# usbswitch.net
KiCad netlist of a schematic drawn in EAGLE
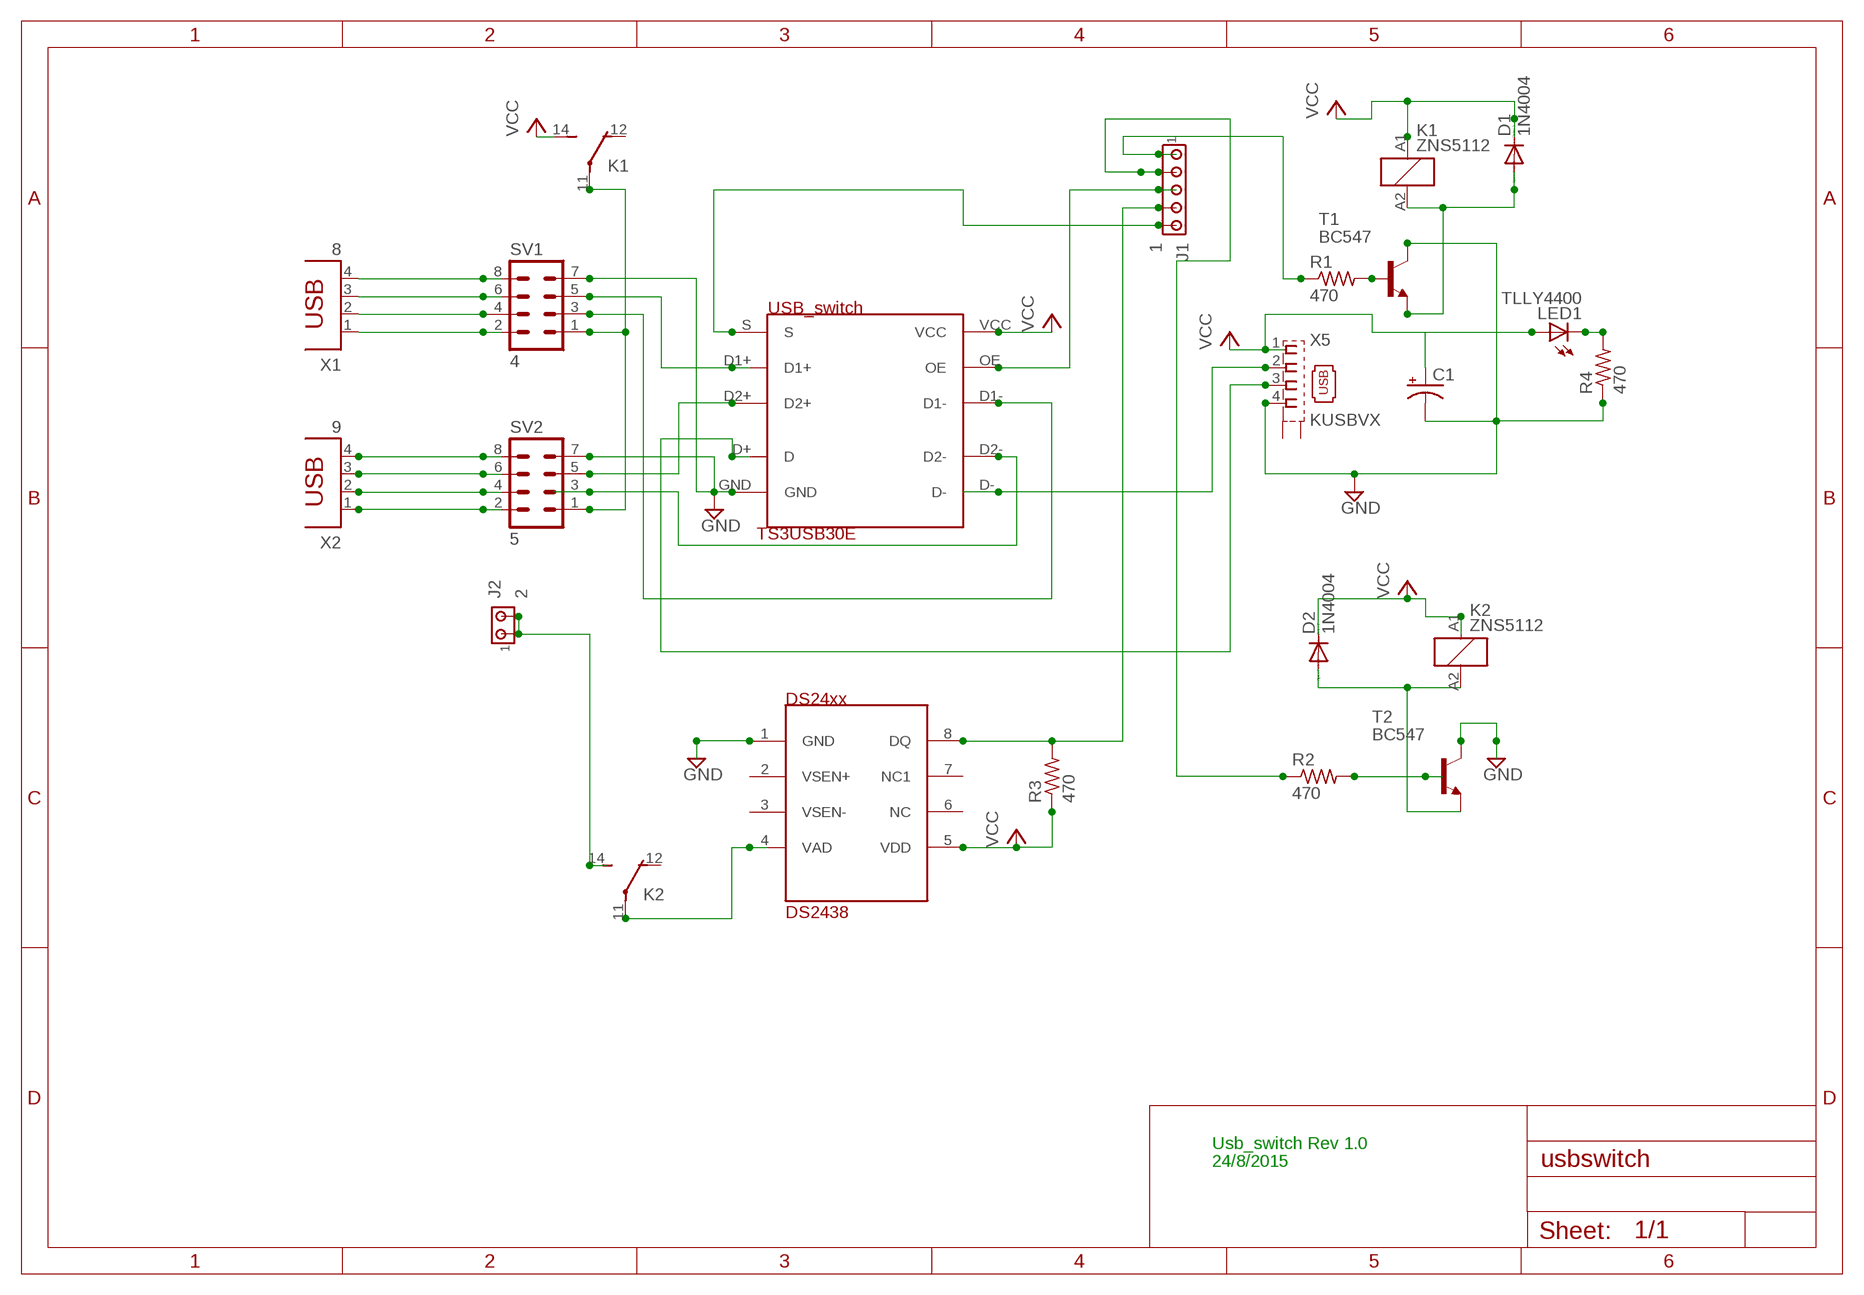
[diagram p0: schematic, sheet 1]

(export (version "E")
  (design (tool "Eeschema 10.0.6"))
  (components
    (comp (ref "C1")
      (value "CPOL-USB45181A")
      (footprint "eagle-import:B45181A")
      (libsource (lib "eagle-import") (part "CPOL-USB45181A"))
    )
    (comp (ref "D1")
      (value "1N4004")
      (footprint "eagle-import:DO41-10")
      (libsource (lib "eagle-import") (part "1N4004"))
    )
    (comp (ref "D2")
      (value "1N4004")
      (footprint "eagle-import:DO41-10")
      (libsource (lib "eagle-import") (part "1N4004"))
    )
    (comp (ref "J1")
      (value "1")
      (footprint "eagle-import:10X05MTA")
      (libsource (lib "eagle-import") (part "MTA05-100"))
    )
    (comp (ref "J2")
      (value "2")
      (footprint "eagle-import:1X2MTA")
      (libsource (lib "eagle-import") (part "MTA02-156"))
    )
    (comp (ref "K1")
      (value "ZNS5112")
      (footprint "eagle-import:ZN5")
      (libsource (lib "eagle-import") (part "ZNS5112"))
    )
    (comp (ref "K2")
      (value "ZNS5112")
      (footprint "eagle-import:ZN5")
      (libsource (lib "eagle-import") (part "ZNS5112"))
    )
    (comp (ref "LED1")
      (value "TLLY4400")
      (footprint "eagle-import:LED3MM")
      (fields (field (name "MF") "VISHAY SEMICONDUCTOR"))
      (libsource (lib "eagle-import") (part "TLLY4400"))
    )
    (comp (ref "R1")
      (value "470")
      (footprint "eagle-import:0204_5")
      (libsource (lib "eagle-import") (part "R-US_0204/5"))
    )
    (comp (ref "R2")
      (value "470")
      (footprint "eagle-import:0204_5")
      (libsource (lib "eagle-import") (part "R-US_0204/5"))
    )
    (comp (ref "R3")
      (value "470")
      (footprint "eagle-import:0204_5")
      (libsource (lib "eagle-import") (part "R-US_0204/5"))
    )
    (comp (ref "R4")
      (value "470")
      (footprint "eagle-import:0204_5")
      (libsource (lib "eagle-import") (part "R-US_0204/5"))
    )
    (comp (ref "SV1")
      (value "4")
      (footprint "eagle-import:MA04-2")
      (libsource (lib "eagle-import") (part "MA04-2"))
    )
    (comp (ref "SV2")
      (value "5")
      (footprint "eagle-import:MA04-2")
      (libsource (lib "eagle-import") (part "MA04-2"))
    )
    (comp (ref "T1")
      (value "BC547")
      (footprint "eagle-import:TO92")
      (libsource (lib "eagle-import") (part "BC547"))
    )
    (comp (ref "T2")
      (value "BC547")
      (footprint "eagle-import:TO92")
      (libsource (lib "eagle-import") (part "BC547"))
    )
    (comp (ref "U$1")
      (value "USB_SWITCH")
      (footprint "eagle-import:PDSO-G10")
      (libsource (lib "eagle-import") (part "myusbswitch_USB_SWITCH"))
    )
    (comp (ref "U$2")
      (value "DS2438")
      (footprint "eagle-import:DS243PKG")
      (libsource (lib "eagle-import") (part "DS2438"))
    )
    (comp (ref "X1")
      (value "8")
      (footprint "eagle-import:PN87520")
      (libsource (lib "eagle-import") (part "PN87520"))
    )
    (comp (ref "X2")
      (value "9")
      (footprint "eagle-import:PN87520")
      (libsource (lib "eagle-import") (part "PN87520"))
    )
    (comp (ref "X5")
      (value "KUSBVX")
      (footprint "eagle-import:KUSBVX")
      (libsource (lib "eagle-import") (part "KUSBVX"))
    )
  )
  (nets
    (net (code "1") (name "GND") (class "Default")
      (node (ref "C1") (pin "-") (pinfunction "-_-") (pintype "passive"))
      (node (ref "R4") (pin "1") (pinfunction "1_1") (pintype "passive"))
      (node (ref "SV1") (pin "7") (pinfunction "7_7") (pintype "passive"))
      (node (ref "SV2") (pin "7") (pinfunction "7_7") (pintype "passive"))
      (node (ref "T1") (pin "3") (pinfunction "C_3") (pintype "passive"))
      (node (ref "T2") (pin "3") (pinfunction "C_3") (pintype "passive"))
      (node (ref "U$1") (pin "GND") (pinfunction "GND_GND") (pintype "bidirectional"))
      (node (ref "U$2") (pin "1") (pinfunction "GND_1") (pintype "bidirectional"))
      (node (ref "X5") (pin "4") (pinfunction "4_4") (pintype "passive"))
    )
    (net (code "2") (name "Net-(J1-Pad1)") (class "Default")
      (node (ref "J1") (pin "1") (pinfunction "1_1") (pintype "passive"))
      (node (ref "R1") (pin "1") (pinfunction "1_1") (pintype "passive"))
    )
    (net (code "3") (name "Net-(J1-Pad2)") (class "Default")
      (node (ref "J1") (pin "2") (pinfunction "2_2") (pintype "passive"))
      (node (ref "R2") (pin "1") (pinfunction "1_1") (pintype "passive"))
    )
    (net (code "4") (name "Net-(J1-Pad3)") (class "Default")
      (node (ref "J1") (pin "3") (pinfunction "3_3") (pintype "passive"))
      (node (ref "U$1") (pin "OE") (pinfunction "OE_OE") (pintype "bidirectional"))
    )
    (net (code "5") (name "Net-(J1-Pad5)") (class "Default")
      (node (ref "J1") (pin "5") (pinfunction "5_5") (pintype "passive"))
      (node (ref "U$1") (pin "S") (pinfunction "S_S") (pintype "bidirectional"))
    )
    (net (code "6") (name "Net-(K1A-2)") (class "Default")
      (node (ref "D1") (pin "A") (pinfunction "A_A") (pintype "passive"))
      (node (ref "K1") (pin "A2") (pinfunction "2_A2") (pintype "passive"))
      (node (ref "T1") (pin "1") (pinfunction "E_1") (pintype "passive"))
    )
    (net (code "7") (name "Net-(K1B-P)") (class "Default")
      (node (ref "K1") (pin "11") (pinfunction "P_11") (pintype "passive"))
      (node (ref "SV1") (pin "1") (pinfunction "1_1") (pintype "passive"))
      (node (ref "SV2") (pin "1") (pinfunction "1_1") (pintype "passive"))
    )
    (net (code "8") (name "Net-(K2A-2)") (class "Default")
      (node (ref "D2") (pin "A") (pinfunction "A_A") (pintype "passive"))
      (node (ref "K2") (pin "A2") (pinfunction "2_A2") (pintype "passive"))
      (node (ref "T2") (pin "1") (pinfunction "E_1") (pintype "passive"))
    )
    (net (code "9") (name "Net-(K2B-P)") (class "Default")
      (node (ref "K2") (pin "11") (pinfunction "P_11") (pintype "passive"))
      (node (ref "U$2") (pin "4") (pinfunction "VAD_4") (pintype "bidirectional"))
    )
    (net (code "10") (name "Net-(K2B-S)") (class "Default")
      (node (ref "J2") (pin "1") (pinfunction "1_1") (pintype "passive"))
      (node (ref "J2") (pin "2") (pinfunction "2_2") (pintype "passive"))
      (node (ref "K2") (pin "14") (pinfunction "S_14") (pintype "passive"))
    )
    (net (code "11") (name "Net-(LED1-C)") (class "Default")
      (node (ref "LED1") (pin "K") (pinfunction "C_K") (pintype "passive"))
      (node (ref "R4") (pin "2") (pinfunction "2_2") (pintype "passive"))
    )
    (net (code "12") (name "Net-(SV1-Pad2)") (class "Default")
      (node (ref "SV1") (pin "2") (pinfunction "2_2") (pintype "passive"))
      (node (ref "X1") (pin "1") (pinfunction "1_1") (pintype "passive"))
    )
    (net (code "13") (name "Net-(SV1-Pad3)") (class "Default")
      (node (ref "SV1") (pin "3") (pinfunction "3_3") (pintype "passive"))
      (node (ref "U$1") (pin "D1-") (pinfunction "D1-_D1-") (pintype "bidirectional"))
    )
    (net (code "14") (name "Net-(SV1-Pad4)") (class "Default")
      (node (ref "SV1") (pin "4") (pinfunction "4_4") (pintype "passive"))
      (node (ref "X1") (pin "2") (pinfunction "2_2") (pintype "passive"))
    )
    (net (code "15") (name "Net-(SV1-Pad5)") (class "Default")
      (node (ref "SV1") (pin "5") (pinfunction "5_5") (pintype "passive"))
      (node (ref "U$1") (pin "D1+") (pinfunction "D1+_D1+") (pintype "bidirectional"))
    )
    (net (code "16") (name "Net-(SV1-Pad6)") (class "Default")
      (node (ref "SV1") (pin "6") (pinfunction "6_6") (pintype "passive"))
      (node (ref "X1") (pin "3") (pinfunction "3_3") (pintype "passive"))
    )
    (net (code "17") (name "Net-(SV1-Pad8)") (class "Default")
      (node (ref "SV1") (pin "8") (pinfunction "8_8") (pintype "passive"))
      (node (ref "X1") (pin "4") (pinfunction "4_4") (pintype "passive"))
    )
    (net (code "18") (name "Net-(SV2-Pad2)") (class "Default")
      (node (ref "SV2") (pin "2") (pinfunction "2_2") (pintype "passive"))
      (node (ref "X2") (pin "1") (pinfunction "1_1") (pintype "passive"))
    )
    (net (code "19") (name "Net-(SV2-Pad3)") (class "Default")
      (node (ref "SV2") (pin "3") (pinfunction "3_3") (pintype "passive"))
      (node (ref "U$1") (pin "D2-") (pinfunction "D2-_D2-") (pintype "bidirectional"))
    )
    (net (code "20") (name "Net-(SV2-Pad4)") (class "Default")
      (node (ref "SV2") (pin "4") (pinfunction "4_4") (pintype "passive"))
      (node (ref "X2") (pin "2") (pinfunction "2_2") (pintype "passive"))
    )
    (net (code "21") (name "Net-(SV2-Pad5)") (class "Default")
      (node (ref "SV2") (pin "5") (pinfunction "5_5") (pintype "passive"))
      (node (ref "U$1") (pin "D2+") (pinfunction "D2+_D2+") (pintype "bidirectional"))
    )
    (net (code "22") (name "Net-(SV2-Pad6)") (class "Default")
      (node (ref "SV2") (pin "6") (pinfunction "6_6") (pintype "passive"))
      (node (ref "X2") (pin "3") (pinfunction "3_3") (pintype "passive"))
    )
    (net (code "23") (name "Net-(SV2-Pad8)") (class "Default")
      (node (ref "SV2") (pin "8") (pinfunction "8_8") (pintype "passive"))
      (node (ref "X2") (pin "4") (pinfunction "4_4") (pintype "passive"))
    )
    (net (code "24") (name "Net-(T1-B)") (class "Default")
      (node (ref "R1") (pin "2") (pinfunction "2_2") (pintype "passive"))
      (node (ref "T1") (pin "2") (pinfunction "B_2") (pintype "passive"))
    )
    (net (code "25") (name "Net-(T2-B)") (class "Default")
      (node (ref "R2") (pin "2") (pinfunction "2_2") (pintype "passive"))
      (node (ref "T2") (pin "2") (pinfunction "B_2") (pintype "passive"))
    )
    (net (code "26") (name "Net-(U$1-D)") (class "Default")
      (node (ref "U$1") (pin "D+") (pinfunction "D_D+") (pintype "bidirectional"))
      (node (ref "X5") (pin "3") (pinfunction "3_3") (pintype "passive"))
    )
    (net (code "27") (name "Net-(U$1-PadD-)") (class "Default")
      (node (ref "U$1") (pin "D-") (pinfunction "D-_D-") (pintype "bidirectional"))
      (node (ref "X5") (pin "2") (pinfunction "2_2") (pintype "passive"))
    )
    (net (code "28") (name "Net-(U$2-DQ)") (class "Default")
      (node (ref "J1") (pin "4") (pinfunction "4_4") (pintype "passive"))
      (node (ref "R3") (pin "2") (pinfunction "2_2") (pintype "passive"))
      (node (ref "U$2") (pin "8") (pinfunction "DQ_8") (pintype "bidirectional"))
    )
    (net (code "29") (name "VCC") (class "Default")
      (node (ref "C1") (pin "+") (pinfunction "+_+") (pintype "passive"))
      (node (ref "D1") (pin "C") (pinfunction "C_C") (pintype "passive"))
      (node (ref "D2") (pin "C") (pinfunction "C_C") (pintype "passive"))
      (node (ref "K1") (pin "14") (pinfunction "S_14") (pintype "passive"))
      (node (ref "K1") (pin "A1") (pinfunction "1_A1") (pintype "passive"))
      (node (ref "K2") (pin "A1") (pinfunction "1_A1") (pintype "passive"))
      (node (ref "LED1") (pin "A") (pinfunction "A_A") (pintype "passive"))
      (node (ref "R3") (pin "1") (pinfunction "1_1") (pintype "passive"))
      (node (ref "U$1") (pin "VCC") (pinfunction "VCC_VCC") (pintype "bidirectional"))
      (node (ref "U$2") (pin "5") (pinfunction "VDD_5") (pintype "bidirectional"))
      (node (ref "X5") (pin "1") (pinfunction "1_1") (pintype "passive"))
    )
    (net (code "30") (name "unconnected-(K1B-O-Pad12)") (class "Default")
      (node (ref "K1") (pin "12") (pinfunction "O_12") (pintype "passive"))
    )
    (net (code "31") (name "unconnected-(K2B-O-Pad12)") (class "Default")
      (node (ref "K2") (pin "12") (pinfunction "O_12") (pintype "passive"))
    )
    (net (code "32") (name "unconnected-(U$2-NC-Pad6)") (class "Default")
      (node (ref "U$2") (pin "6") (pinfunction "NC_6") (pintype "bidirectional"))
    )
    (net (code "33") (name "unconnected-(U$2-NC1-Pad7)") (class "Default")
      (node (ref "U$2") (pin "7") (pinfunction "NC1_7") (pintype "bidirectional"))
    )
    (net (code "34") (name "unconnected-(U$2-VSEN+-Pad2)") (class "Default")
      (node (ref "U$2") (pin "2") (pinfunction "VSEN+_2") (pintype "bidirectional"))
    )
    (net (code "35") (name "unconnected-(U$2-VSEN--Pad3)") (class "Default")
      (node (ref "U$2") (pin "3") (pinfunction "VSEN-_3") (pintype "bidirectional"))
    )
    (net (code "36") (name "unconnected-(X5-S1-PadM1)") (class "Default")
      (node (ref "X5") (pin "M1") (pinfunction "S1_M1") (pintype "passive"))
    )
    (net (code "37") (name "unconnected-(X5-S2-PadM2)") (class "Default")
      (node (ref "X5") (pin "M2") (pinfunction "S2_M2") (pintype "passive"))
    )
  )
)
